# TEENSY_1_1.net
KiCad netlist of a schematic drawn in Altium Designer
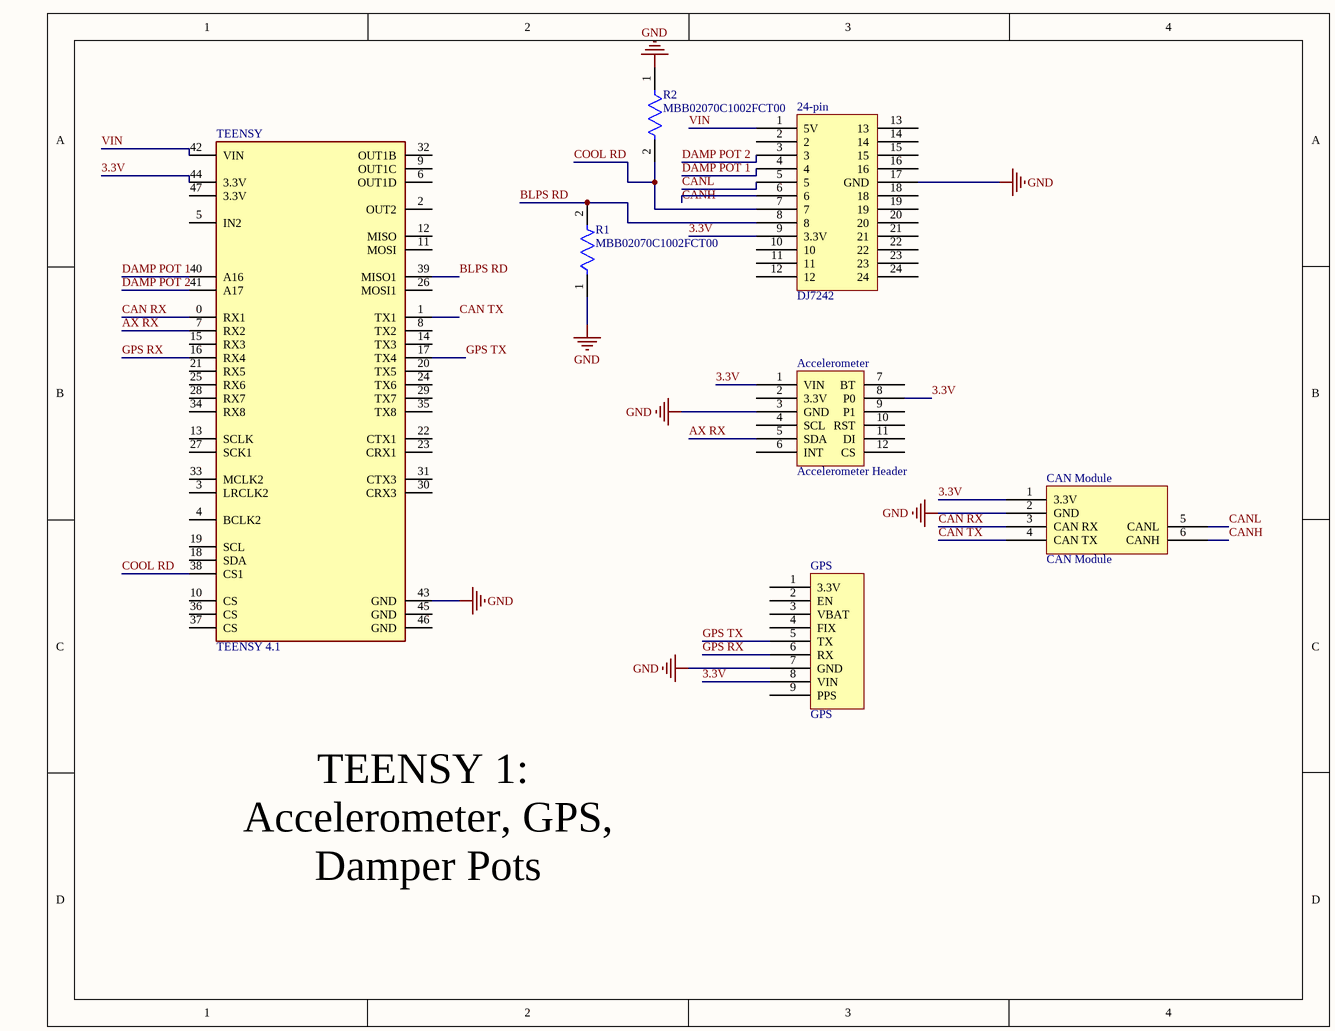
[diagram p0: TEENSY 1.1.SchDoc]

(export (version "E")
  (design (tool "Eeschema 10.0.6"))
  (components
    (comp (ref "24-pin")
      (value "DJ7242")
      (footprint "DJ7242-Footprint-1")
      (description "24-pin connector")
      (libsource (lib "cmabey15") (part "DJ7242-Symbol-1"))
    )
    (comp (ref "Accelerometer")
      (value "Accelerometer Header")
      (footprint "Accelerometer Header-Footprint-1")
      (description "Header for Adafruit Accelerometer")
      (libsource (lib "cmabey15") (part "Accel"))
    )
    (comp (ref "CAN Module")
      (value "CAN Module")
      (footprint "CAN Module-Footprint-1")
      (description "CAN waveshare")
      (libsource (lib "cmabey15") (part "CAN Module-Symbol-1"))
    )
    (comp (ref "GPS")
      (value "GPS")
      (footprint "GPS-Footprint-1")
      (description "Adafruit GPS chip")
      (libsource (lib "cmabey15") (part "GPS"))
    )
    (comp (ref "R1")
      (value "MBB02070C1002FCT00")
      (footprint "FP-MBB0207-MFG")
      (description "RES 10K OHM 0.6W 1% AXIAL")
      (fields (field (name "TOLERANCE") "1%"))
      (libsource (lib "Altium Content Vault") (part "1029c3af85768c4190bb7ad29bc67b5"))
    )
    (comp (ref "R2")
      (value "MBB02070C1002FCT00")
      (footprint "FP-MBB0207-MFG")
      (description "RES 10K OHM 0.6W 1% AXIAL")
      (fields (field (name "TOLERANCE") "1%"))
      (libsource (lib "Altium Content Vault") (part "1029c3af85768c4190bb7ad29bc67b5"))
    )
    (comp (ref "TEENSY")
      (value "TEENSY 4.1")
      (footprint "FP-DEV-16996-MFG")
      (description "TEENSY 4.1 (HEADERS)")
      (libsource (lib "Altium Content Vault") (part "080115a1ce54750370cf87ec145ee29"))
    )
  )
  (nets
    (net (code "1") (name "/3.3V") (class "Default")
      (node (ref "24-pin") (pin "9") (pinfunction "3.3V_9") (pintype "passive"))
      (node (ref "Accelerometer") (pin "1") (pinfunction "VIN_1") (pintype "passive"))
      (node (ref "Accelerometer") (pin "8") (pinfunction "P0_8") (pintype "passive"))
      (node (ref "CAN Module") (pin "1") (pinfunction "3.3V_1") (pintype "passive"))
      (node (ref "GPS") (pin "8") (pinfunction "VIN_8") (pintype "passive"))
      (node (ref "TEENSY") (pin "44") (pinfunction "3.3V_44") (pintype "passive"))
    )
    (net (code "2") (name "/AX RX") (class "Default")
      (node (ref "Accelerometer") (pin "5") (pinfunction "SDA_5") (pintype "passive"))
      (node (ref "TEENSY") (pin "7") (pinfunction "RX2_7") (pintype "passive"))
    )
    (net (code "3") (name "/BLPS RD") (class "Default")
      (node (ref "24-pin") (pin "8") (pinfunction "8_8") (pintype "passive"))
      (node (ref "R1") (pin "2") (pinfunction "2_2") (pintype "passive"))
      (node (ref "TEENSY") (pin "39") (pinfunction "MISO1_39") (pintype "passive"))
    )
    (net (code "4") (name "/CAN RX") (class "Default")
      (node (ref "CAN Module") (pin "3") (pinfunction "CAN_RX_3") (pintype "passive"))
      (node (ref "TEENSY") (pin "0") (pinfunction "RX1_0") (pintype "passive"))
    )
    (net (code "5") (name "/CAN TX") (class "Default")
      (node (ref "CAN Module") (pin "4") (pinfunction "CAN_TX_4") (pintype "passive"))
      (node (ref "TEENSY") (pin "1") (pinfunction "TX1_1") (pintype "passive"))
    )
    (net (code "6") (name "/CANH") (class "Default")
      (node (ref "24-pin") (pin "6") (pinfunction "6_6") (pintype "passive"))
      (node (ref "CAN Module") (pin "6") (pinfunction "CANH_6") (pintype "passive"))
    )
    (net (code "7") (name "/CANL") (class "Default")
      (node (ref "24-pin") (pin "5") (pinfunction "5_5") (pintype "passive"))
      (node (ref "CAN Module") (pin "5") (pinfunction "CANL_5") (pintype "passive"))
    )
    (net (code "8") (name "/COOL RD") (class "Default")
      (node (ref "24-pin") (pin "7") (pinfunction "7_7") (pintype "passive"))
      (node (ref "R2") (pin "2") (pinfunction "2_2") (pintype "passive"))
      (node (ref "TEENSY") (pin "38") (pinfunction "CS1_38") (pintype "passive"))
    )
    (net (code "9") (name "/DAMP POT 1") (class "Default")
      (node (ref "24-pin") (pin "4") (pinfunction "4_4") (pintype "passive"))
      (node (ref "TEENSY") (pin "40") (pinfunction "A16_40") (pintype "passive"))
    )
    (net (code "10") (name "/DAMP POT 2") (class "Default")
      (node (ref "24-pin") (pin "3") (pinfunction "3_3") (pintype "passive"))
      (node (ref "TEENSY") (pin "41") (pinfunction "A17_41") (pintype "passive"))
    )
    (net (code "11") (name "/GPS RX") (class "Default")
      (node (ref "GPS") (pin "6") (pinfunction "RX_6") (pintype "passive"))
      (node (ref "TEENSY") (pin "16") (pinfunction "RX4_16") (pintype "passive"))
    )
    (net (code "12") (name "/GPS TX") (class "Default")
      (node (ref "GPS") (pin "5") (pinfunction "TX_5") (pintype "passive"))
      (node (ref "TEENSY") (pin "17") (pinfunction "TX4_17") (pintype "passive"))
    )
    (net (code "13") (name "/VIN") (class "Default")
      (node (ref "24-pin") (pin "1") (pinfunction "5V_1") (pintype "passive"))
      (node (ref "TEENSY") (pin "42") (pinfunction "VIN_42") (pintype "passive"))
    )
    (net (code "14") (name "GND") (class "Default")
      (node (ref "24-pin") (pin "17") (pinfunction "GND_17") (pintype "passive"))
      (node (ref "Accelerometer") (pin "3") (pinfunction "GND_3") (pintype "passive"))
      (node (ref "CAN Module") (pin "2") (pinfunction "GND_2") (pintype "passive"))
      (node (ref "GPS") (pin "7") (pinfunction "GND_7") (pintype "passive"))
      (node (ref "R1") (pin "1") (pinfunction "1_1") (pintype "passive"))
      (node (ref "R2") (pin "1") (pinfunction "1_1") (pintype "passive"))
      (node (ref "TEENSY") (pin "43") (pinfunction "GND_43") (pintype "passive"))
    )
    (net (code "15") (name "unconnected-(24-pin-Pad2)") (class "Default")
      (node (ref "24-pin") (pin "2") (pinfunction "2_2") (pintype "passive"))
    )
    (net (code "16") (name "unconnected-(24-pin-Pad10)") (class "Default")
      (node (ref "24-pin") (pin "10") (pinfunction "10_10") (pintype "passive"))
    )
    (net (code "17") (name "unconnected-(24-pin-Pad11)") (class "Default")
      (node (ref "24-pin") (pin "11") (pinfunction "11_11") (pintype "passive"))
    )
    (net (code "18") (name "unconnected-(24-pin-Pad12)") (class "Default")
      (node (ref "24-pin") (pin "12") (pinfunction "12_12") (pintype "passive"))
    )
    (net (code "19") (name "unconnected-(24-pin-Pad13)") (class "Default")
      (node (ref "24-pin") (pin "13") (pinfunction "13_13") (pintype "passive"))
    )
    (net (code "20") (name "unconnected-(24-pin-Pad14)") (class "Default")
      (node (ref "24-pin") (pin "14") (pinfunction "14_14") (pintype "passive"))
    )
    (net (code "21") (name "unconnected-(24-pin-Pad15)") (class "Default")
      (node (ref "24-pin") (pin "15") (pinfunction "15_15") (pintype "passive"))
    )
    (net (code "22") (name "unconnected-(24-pin-Pad16)") (class "Default")
      (node (ref "24-pin") (pin "16") (pinfunction "16_16") (pintype "passive"))
    )
    (net (code "23") (name "unconnected-(24-pin-Pad18)") (class "Default")
      (node (ref "24-pin") (pin "18") (pinfunction "18_18") (pintype "passive"))
    )
    (net (code "24") (name "unconnected-(24-pin-Pad19)") (class "Default")
      (node (ref "24-pin") (pin "19") (pinfunction "19_19") (pintype "passive"))
    )
    (net (code "25") (name "unconnected-(24-pin-Pad20)") (class "Default")
      (node (ref "24-pin") (pin "20") (pinfunction "20_20") (pintype "passive"))
    )
    (net (code "26") (name "unconnected-(24-pin-Pad21)") (class "Default")
      (node (ref "24-pin") (pin "21") (pinfunction "21_21") (pintype "passive"))
    )
    (net (code "27") (name "unconnected-(24-pin-Pad22)") (class "Default")
      (node (ref "24-pin") (pin "22") (pinfunction "22_22") (pintype "passive"))
    )
    (net (code "28") (name "unconnected-(24-pin-Pad23)") (class "Default")
      (node (ref "24-pin") (pin "23") (pinfunction "23_23") (pintype "passive"))
    )
    (net (code "29") (name "unconnected-(24-pin-Pad24)") (class "Default")
      (node (ref "24-pin") (pin "24") (pinfunction "24_24") (pintype "passive"))
    )
    (net (code "30") (name "unconnected-(Accelerometer-3.3V-Pad2)") (class "Default")
      (node (ref "Accelerometer") (pin "2") (pinfunction "3.3V_2") (pintype "passive"))
    )
    (net (code "31") (name "unconnected-(Accelerometer-BT-Pad7)") (class "Default")
      (node (ref "Accelerometer") (pin "7") (pinfunction "BT_7") (pintype "passive"))
    )
    (net (code "32") (name "unconnected-(Accelerometer-CS-Pad12)") (class "Default")
      (node (ref "Accelerometer") (pin "12") (pinfunction "CS_12") (pintype "passive"))
    )
    (net (code "33") (name "unconnected-(Accelerometer-DI-Pad11)") (class "Default")
      (node (ref "Accelerometer") (pin "11") (pinfunction "DI_11") (pintype "passive"))
    )
    (net (code "34") (name "unconnected-(Accelerometer-INT-Pad6)") (class "Default")
      (node (ref "Accelerometer") (pin "6") (pinfunction "INT_6") (pintype "passive"))
    )
    (net (code "35") (name "unconnected-(Accelerometer-P1-Pad9)") (class "Default")
      (node (ref "Accelerometer") (pin "9") (pinfunction "P1_9") (pintype "passive"))
    )
    (net (code "36") (name "unconnected-(Accelerometer-RST-Pad10)") (class "Default")
      (node (ref "Accelerometer") (pin "10") (pinfunction "RST_10") (pintype "passive"))
    )
    (net (code "37") (name "unconnected-(Accelerometer-SCL-Pad4)") (class "Default")
      (node (ref "Accelerometer") (pin "4") (pinfunction "SCL_4") (pintype "passive"))
    )
    (net (code "38") (name "unconnected-(GPS-3.3V-Pad1)") (class "Default")
      (node (ref "GPS") (pin "1") (pinfunction "3.3V_1") (pintype "passive"))
    )
    (net (code "39") (name "unconnected-(GPS-EN-Pad2)") (class "Default")
      (node (ref "GPS") (pin "2") (pinfunction "EN_2") (pintype "passive"))
    )
    (net (code "40") (name "unconnected-(GPS-FIX-Pad4)") (class "Default")
      (node (ref "GPS") (pin "4") (pinfunction "FIX_4") (pintype "passive"))
    )
    (net (code "41") (name "unconnected-(GPS-PPS-Pad9)") (class "Default")
      (node (ref "GPS") (pin "9") (pinfunction "PPS_9") (pintype "passive"))
    )
    (net (code "42") (name "unconnected-(GPS-VBAT-Pad3)") (class "Default")
      (node (ref "GPS") (pin "3") (pinfunction "VBAT_3") (pintype "passive"))
    )
    (net (code "43") (name "unconnected-(TEENSY-3.3V-Pad47)") (class "Default")
      (node (ref "TEENSY") (pin "47") (pinfunction "3.3V_47") (pintype "passive"))
    )
    (net (code "44") (name "unconnected-(TEENSY-BCLK2-Pad4)") (class "Default")
      (node (ref "TEENSY") (pin "4") (pinfunction "BCLK2_4") (pintype "passive"))
    )
    (net (code "45") (name "unconnected-(TEENSY-CRX1-Pad23)") (class "Default")
      (node (ref "TEENSY") (pin "23") (pinfunction "CRX1_23") (pintype "passive"))
    )
    (net (code "46") (name "unconnected-(TEENSY-CRX3-Pad30)") (class "Default")
      (node (ref "TEENSY") (pin "30") (pinfunction "CRX3_30") (pintype "passive"))
    )
    (net (code "47") (name "unconnected-(TEENSY-CS-Pad10)") (class "Default")
      (node (ref "TEENSY") (pin "10") (pinfunction "CS_10") (pintype "passive"))
    )
    (net (code "48") (name "unconnected-(TEENSY-CS-Pad36)") (class "Default")
      (node (ref "TEENSY") (pin "36") (pinfunction "CS_36") (pintype "passive"))
    )
    (net (code "49") (name "unconnected-(TEENSY-CS-Pad37)") (class "Default")
      (node (ref "TEENSY") (pin "37") (pinfunction "CS_37") (pintype "passive"))
    )
    (net (code "50") (name "unconnected-(TEENSY-CTX1-Pad22)") (class "Default")
      (node (ref "TEENSY") (pin "22") (pinfunction "CTX1_22") (pintype "passive"))
    )
    (net (code "51") (name "unconnected-(TEENSY-CTX3-Pad31)") (class "Default")
      (node (ref "TEENSY") (pin "31") (pinfunction "CTX3_31") (pintype "passive"))
    )
    (net (code "52") (name "unconnected-(TEENSY-GND-Pad45)") (class "Default")
      (node (ref "TEENSY") (pin "45") (pinfunction "GND_45") (pintype "passive"))
    )
    (net (code "53") (name "unconnected-(TEENSY-GND-Pad46)") (class "Default")
      (node (ref "TEENSY") (pin "46") (pinfunction "GND_46") (pintype "passive"))
    )
    (net (code "54") (name "unconnected-(TEENSY-IN2-Pad5)") (class "Default")
      (node (ref "TEENSY") (pin "5") (pinfunction "IN2_5") (pintype "passive"))
    )
    (net (code "55") (name "unconnected-(TEENSY-LRCLK2-Pad3)") (class "Default")
      (node (ref "TEENSY") (pin "3") (pinfunction "LRCLK2_3") (pintype "passive"))
    )
    (net (code "56") (name "unconnected-(TEENSY-MCLK2-Pad33)") (class "Default")
      (node (ref "TEENSY") (pin "33") (pinfunction "MCLK2_33") (pintype "passive"))
    )
    (net (code "57") (name "unconnected-(TEENSY-MISO-Pad12)") (class "Default")
      (node (ref "TEENSY") (pin "12") (pinfunction "MISO_12") (pintype "passive"))
    )
    (net (code "58") (name "unconnected-(TEENSY-MOSI-Pad11)") (class "Default")
      (node (ref "TEENSY") (pin "11") (pinfunction "MOSI_11") (pintype "passive"))
    )
    (net (code "59") (name "unconnected-(TEENSY-MOSI1-Pad26)") (class "Default")
      (node (ref "TEENSY") (pin "26") (pinfunction "MOSI1_26") (pintype "passive"))
    )
    (net (code "60") (name "unconnected-(TEENSY-OUT1B-Pad32)") (class "Default")
      (node (ref "TEENSY") (pin "32") (pinfunction "OUT1B_32") (pintype "passive"))
    )
    (net (code "61") (name "unconnected-(TEENSY-OUT1C-Pad9)") (class "Default")
      (node (ref "TEENSY") (pin "9") (pinfunction "OUT1C_9") (pintype "passive"))
    )
    (net (code "62") (name "unconnected-(TEENSY-OUT1D-Pad6)") (class "Default")
      (node (ref "TEENSY") (pin "6") (pinfunction "OUT1D_6") (pintype "passive"))
    )
    (net (code "63") (name "unconnected-(TEENSY-OUT2-Pad2)") (class "Default")
      (node (ref "TEENSY") (pin "2") (pinfunction "OUT2_2") (pintype "passive"))
    )
    (net (code "64") (name "unconnected-(TEENSY-RX3-Pad15)") (class "Default")
      (node (ref "TEENSY") (pin "15") (pinfunction "RX3_15") (pintype "passive"))
    )
    (net (code "65") (name "unconnected-(TEENSY-RX5-Pad21)") (class "Default")
      (node (ref "TEENSY") (pin "21") (pinfunction "RX5_21") (pintype "passive"))
    )
    (net (code "66") (name "unconnected-(TEENSY-RX6-Pad25)") (class "Default")
      (node (ref "TEENSY") (pin "25") (pinfunction "RX6_25") (pintype "passive"))
    )
    (net (code "67") (name "unconnected-(TEENSY-RX7-Pad28)") (class "Default")
      (node (ref "TEENSY") (pin "28") (pinfunction "RX7_28") (pintype "passive"))
    )
    (net (code "68") (name "unconnected-(TEENSY-RX8-Pad34)") (class "Default")
      (node (ref "TEENSY") (pin "34") (pinfunction "RX8_34") (pintype "passive"))
    )
    (net (code "69") (name "unconnected-(TEENSY-SCK1-Pad27)") (class "Default")
      (node (ref "TEENSY") (pin "27") (pinfunction "SCK1_27") (pintype "passive"))
    )
    (net (code "70") (name "unconnected-(TEENSY-SCL-Pad19)") (class "Default")
      (node (ref "TEENSY") (pin "19") (pinfunction "SCL_19") (pintype "passive"))
    )
    (net (code "71") (name "unconnected-(TEENSY-SCLK-Pad13)") (class "Default")
      (node (ref "TEENSY") (pin "13") (pinfunction "SCLK_13") (pintype "passive"))
    )
    (net (code "72") (name "unconnected-(TEENSY-SDA-Pad18)") (class "Default")
      (node (ref "TEENSY") (pin "18") (pinfunction "SDA_18") (pintype "passive"))
    )
    (net (code "73") (name "unconnected-(TEENSY-TX2-Pad8)") (class "Default")
      (node (ref "TEENSY") (pin "8") (pinfunction "TX2_8") (pintype "passive"))
    )
    (net (code "74") (name "unconnected-(TEENSY-TX3-Pad14)") (class "Default")
      (node (ref "TEENSY") (pin "14") (pinfunction "TX3_14") (pintype "passive"))
    )
    (net (code "75") (name "unconnected-(TEENSY-TX5-Pad20)") (class "Default")
      (node (ref "TEENSY") (pin "20") (pinfunction "TX5_20") (pintype "passive"))
    )
    (net (code "76") (name "unconnected-(TEENSY-TX6-Pad24)") (class "Default")
      (node (ref "TEENSY") (pin "24") (pinfunction "TX6_24") (pintype "passive"))
    )
    (net (code "77") (name "unconnected-(TEENSY-TX7-Pad29)") (class "Default")
      (node (ref "TEENSY") (pin "29") (pinfunction "TX7_29") (pintype "passive"))
    )
    (net (code "78") (name "unconnected-(TEENSY-TX8-Pad35)") (class "Default")
      (node (ref "TEENSY") (pin "35") (pinfunction "TX8_35") (pintype "passive"))
    )
  )
)
